# LB_BIT_i5_SLIDEDIMMER-v02_rev1.net
KiCad netlist of a schematic drawn in EAGLE
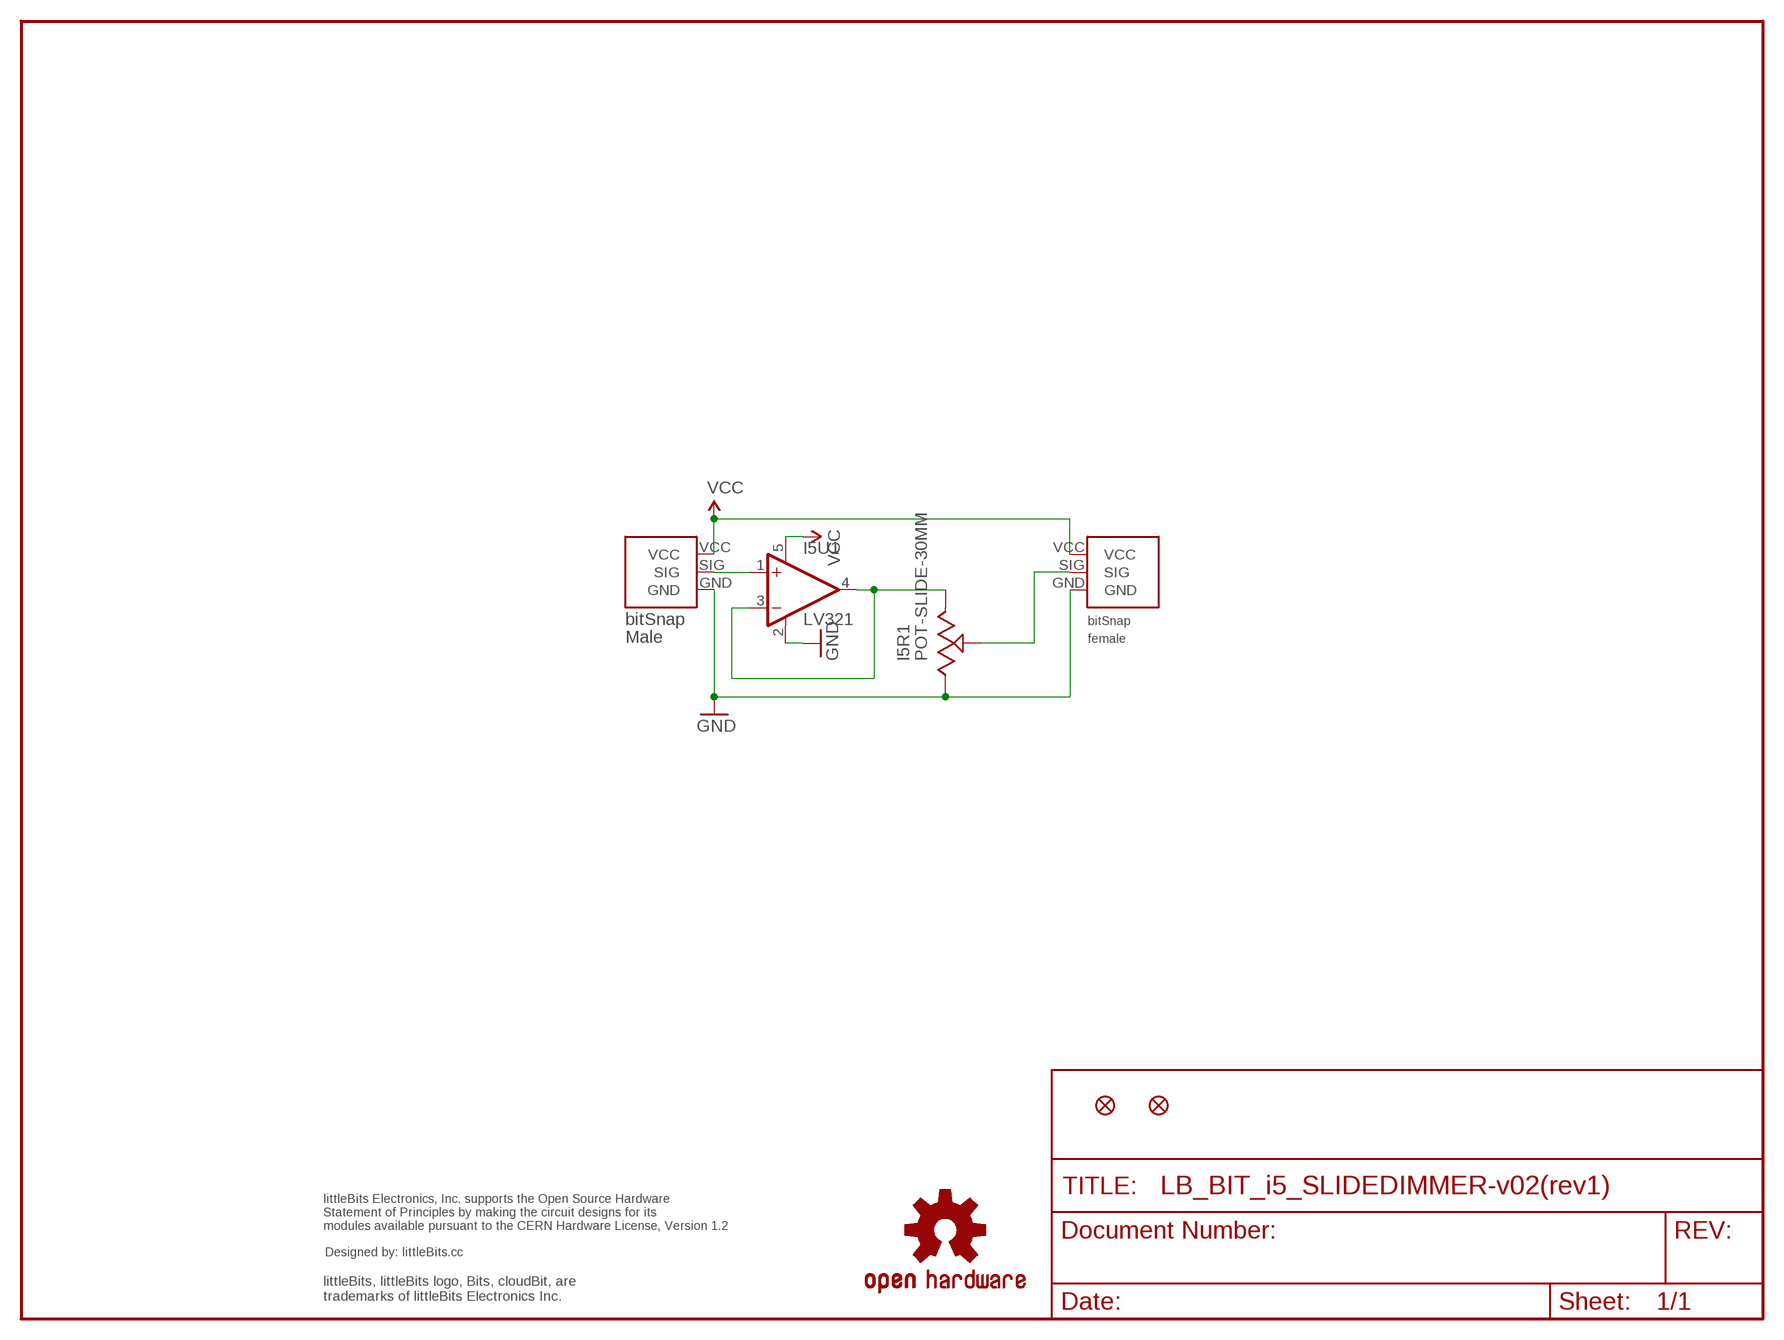
[diagram p0: schematic, sheet 1]

(export (version "E")
  (design (tool "Eeschema 10.0.6"))
  (components
    (comp (ref "I5BSF")
      (value "BITSNAP_FEMALE")
      (footprint "eagle-import:BITSNAP_FEMALE")
      (libsource (lib "eagle-import") (part "BITSNAP_FEMALE"))
    )
    (comp (ref "I5BSM")
      (value "BITSNAP_MALE")
      (footprint "eagle-import:BITSNAP_MALE")
      (libsource (lib "eagle-import") (part "BITSNAP_MALE"))
    )
    (comp (ref "I5FD1")
      (value "FIDUCIAL1X2")
      (footprint "eagle-import:FIDUCIAL-1X2")
      (libsource (lib "eagle-import") (part "FIDUCIAL1X2"))
    )
    (comp (ref "I5FD2")
      (value "FIDUCIAL1X2")
      (footprint "eagle-import:FIDUCIAL-1X2")
      (libsource (lib "eagle-import") (part "FIDUCIAL1X2"))
    )
    (comp (ref "I5R1")
      (value "POT-SLIDE-30MM")
      (footprint "eagle-import:POT-SLIDE-30MM")
      (libsource (lib "eagle-import") (part "POT-SLIDE-30MM"))
    )
    (comp (ref "I5U1")
      (value "LV321")
      (footprint "eagle-import:SC70-5")
      (libsource (lib "eagle-import") (part "LV321"))
    )
    (comp (ref "U$5")
      (value "OSHW-LOGOL")
      (footprint "eagle-import:OSHW-LOGO-L")
      (libsource (lib "eagle-import") (part "OSHW-LOGOL"))
    )
    (comp (ref "U$6")
      (value "OSHWCREDIT")
      (footprint "eagle-import:OSHWCREDIT")
      (libsource (lib "eagle-import") (part "OSHWCREDIT"))
    )
  )
  (nets
    (net (code "1") (name "GND") (class "Default")
      (node (ref "I5BSF") (pin "GND") (pinfunction "GND_GND") (pintype "bidirectional"))
      (node (ref "I5BSM") (pin "GND") (pinfunction "GND_GND") (pintype "bidirectional"))
      (node (ref "I5R1") (pin "3") (pinfunction "3_3") (pintype "passive"))
      (node (ref "I5U1") (pin "2") (pinfunction "V-_2") (pintype "power_in"))
    )
    (net (code "2") (name "Net-(I5BSF-PadSIG)") (class "Default")
      (node (ref "I5BSF") (pin "SIG") (pinfunction "SIG_SIG") (pintype "bidirectional"))
      (node (ref "I5R1") (pin "2") (pinfunction "2_2") (pintype "passive"))
    )
    (net (code "3") (name "Net-(I5U1-+IN)") (class "Default")
      (node (ref "I5BSM") (pin "SIG") (pinfunction "SIG_SIG") (pintype "bidirectional"))
      (node (ref "I5U1") (pin "1") (pinfunction "+IN_1") (pintype "input"))
    )
    (net (code "4") (name "Net-(I5U1--IN)") (class "Default")
      (node (ref "I5R1") (pin "1") (pinfunction "1_1") (pintype "passive"))
      (node (ref "I5U1") (pin "3") (pinfunction "-IN_3") (pintype "input"))
      (node (ref "I5U1") (pin "4") (pinfunction "OUT_4") (pintype "output"))
    )
    (net (code "5") (name "VCC") (class "Default")
      (node (ref "I5BSF") (pin "VCC") (pinfunction "VCC_VCC") (pintype "bidirectional"))
      (node (ref "I5BSM") (pin "VCC") (pinfunction "VCC_VCC") (pintype "bidirectional"))
      (node (ref "I5U1") (pin "5") (pinfunction "V+_5") (pintype "power_in"))
    )
  )
)
